# Adafruit_NeoPixel_8_Stick.net
KiCad netlist of a schematic drawn in EAGLE
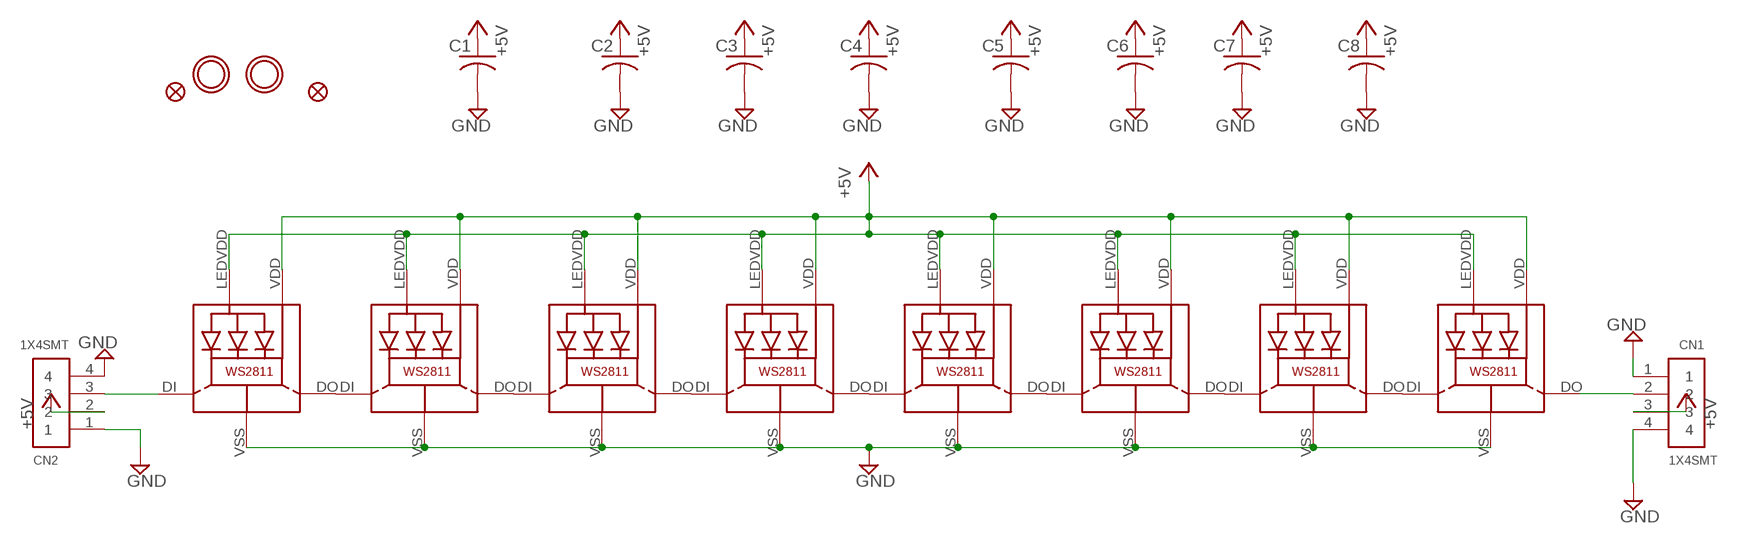
[diagram p0: schematic, sheet 1]

(export (version "E")
  (design (tool "Eeschema 10.0.6"))
  (components
    (comp (ref "C1")
      (value "C-USC0805K")
      (footprint "eagle-import:C0805K")
      (libsource (lib "eagle-import") (part "C-USC0805K"))
    )
    (comp (ref "C2")
      (value "C-USC0805K")
      (footprint "eagle-import:C0805K")
      (libsource (lib "eagle-import") (part "C-USC0805K"))
    )
    (comp (ref "C3")
      (value "C-USC0805K")
      (footprint "eagle-import:C0805K")
      (libsource (lib "eagle-import") (part "C-USC0805K"))
    )
    (comp (ref "C4")
      (value "C-USC0805K")
      (footprint "eagle-import:C0805K")
      (libsource (lib "eagle-import") (part "C-USC0805K"))
    )
    (comp (ref "C5")
      (value "C-USC0805K")
      (footprint "eagle-import:C0805K")
      (libsource (lib "eagle-import") (part "C-USC0805K"))
    )
    (comp (ref "C6")
      (value "C-USC0805K")
      (footprint "eagle-import:C0805K")
      (libsource (lib "eagle-import") (part "C-USC0805K"))
    )
    (comp (ref "C7")
      (value "C-USC0805K")
      (footprint "eagle-import:C0805K")
      (libsource (lib "eagle-import") (part "C-USC0805K"))
    )
    (comp (ref "C8")
      (value "C-USC0805K")
      (footprint "eagle-import:C0805K")
      (libsource (lib "eagle-import") (part "C-USC0805K"))
    )
    (comp (ref "CN1")
      (value "1X4SMT")
      (footprint "eagle-import:1X4-SMT")
      (libsource (lib "eagle-import") (part "1X4SMT"))
    )
    (comp (ref "CN2")
      (value "1X4SMT")
      (footprint "eagle-import:1X4-SMT")
      (libsource (lib "eagle-import") (part "1X4SMT"))
    )
    (comp (ref "FID1")
      (value "FIDUCIAL\"\"")
      (footprint "eagle-import:FIDUCIAL_1MM")
      (libsource (lib "eagle-import") (part "FIDUCIAL{dblquote}{dblquote}"))
    )
    (comp (ref "FID3")
      (value "FIDUCIAL\"\"")
      (footprint "eagle-import:FIDUCIAL_1MM")
      (libsource (lib "eagle-import") (part "FIDUCIAL{dblquote}{dblquote}"))
    )
    (comp (ref "LED1")
      (value "WS28115050")
      (footprint "eagle-import:WS28115050")
      (libsource (lib "eagle-import") (part "WS28115050"))
    )
    (comp (ref "LED2")
      (value "WS28115050")
      (footprint "eagle-import:WS28115050")
      (libsource (lib "eagle-import") (part "WS28115050"))
    )
    (comp (ref "LED3")
      (value "WS28115050")
      (footprint "eagle-import:WS28115050")
      (libsource (lib "eagle-import") (part "WS28115050"))
    )
    (comp (ref "LED4")
      (value "WS28115050")
      (footprint "eagle-import:WS28115050")
      (libsource (lib "eagle-import") (part "WS28115050"))
    )
    (comp (ref "LED5")
      (value "WS28115050")
      (footprint "eagle-import:WS28115050")
      (libsource (lib "eagle-import") (part "WS28115050"))
    )
    (comp (ref "LED6")
      (value "WS28115050")
      (footprint "eagle-import:WS28115050")
      (libsource (lib "eagle-import") (part "WS28115050"))
    )
    (comp (ref "LED7")
      (value "WS28115050")
      (footprint "eagle-import:WS28115050")
      (libsource (lib "eagle-import") (part "WS28115050"))
    )
    (comp (ref "LED8")
      (value "WS28115050")
      (footprint "eagle-import:WS28115050")
      (libsource (lib "eagle-import") (part "WS28115050"))
    )
    (comp (ref "U$2")
      (value "MOUNTINGHOLE2.0")
      (footprint "eagle-import:MOUNTINGHOLE_2.0_PLATED")
      (libsource (lib "eagle-import") (part "MOUNTINGHOLE2.0"))
    )
    (comp (ref "U$3")
      (value "MOUNTINGHOLE2.0")
      (footprint "eagle-import:MOUNTINGHOLE_2.0_PLATED")
      (libsource (lib "eagle-import") (part "MOUNTINGHOLE2.0"))
    )
  )
  (nets
    (net (code "1") (name "+5V") (class "Default")
      (node (ref "C1") (pin "1") (pinfunction "1_1") (pintype "passive"))
      (node (ref "C2") (pin "1") (pinfunction "1_1") (pintype "passive"))
      (node (ref "C3") (pin "1") (pinfunction "1_1") (pintype "passive"))
      (node (ref "C4") (pin "1") (pinfunction "1_1") (pintype "passive"))
      (node (ref "C5") (pin "1") (pinfunction "1_1") (pintype "passive"))
      (node (ref "C6") (pin "1") (pinfunction "1_1") (pintype "passive"))
      (node (ref "C7") (pin "1") (pinfunction "1_1") (pintype "passive"))
      (node (ref "C8") (pin "1") (pinfunction "1_1") (pintype "passive"))
      (node (ref "CN1") (pin "3") (pinfunction "3_3") (pintype "bidirectional"))
      (node (ref "CN2") (pin "2") (pinfunction "2_2") (pintype "bidirectional"))
      (node (ref "LED1") (pin "LEDVDD") (pinfunction "LEDVDD_LEDVDD") (pintype "power_in"))
      (node (ref "LED1") (pin "VDD") (pinfunction "VDD_VDD") (pintype "power_in"))
      (node (ref "LED2") (pin "LEDVDD") (pinfunction "LEDVDD_LEDVDD") (pintype "power_in"))
      (node (ref "LED2") (pin "VDD") (pinfunction "VDD_VDD") (pintype "power_in"))
      (node (ref "LED3") (pin "LEDVDD") (pinfunction "LEDVDD_LEDVDD") (pintype "power_in"))
      (node (ref "LED3") (pin "VDD") (pinfunction "VDD_VDD") (pintype "power_in"))
      (node (ref "LED4") (pin "LEDVDD") (pinfunction "LEDVDD_LEDVDD") (pintype "power_in"))
      (node (ref "LED4") (pin "VDD") (pinfunction "VDD_VDD") (pintype "power_in"))
      (node (ref "LED5") (pin "LEDVDD") (pinfunction "LEDVDD_LEDVDD") (pintype "power_in"))
      (node (ref "LED5") (pin "VDD") (pinfunction "VDD_VDD") (pintype "power_in"))
      (node (ref "LED6") (pin "LEDVDD") (pinfunction "LEDVDD_LEDVDD") (pintype "power_in"))
      (node (ref "LED6") (pin "VDD") (pinfunction "VDD_VDD") (pintype "power_in"))
      (node (ref "LED7") (pin "LEDVDD") (pinfunction "LEDVDD_LEDVDD") (pintype "power_in"))
      (node (ref "LED7") (pin "VDD") (pinfunction "VDD_VDD") (pintype "power_in"))
      (node (ref "LED8") (pin "LEDVDD") (pinfunction "LEDVDD_LEDVDD") (pintype "power_in"))
      (node (ref "LED8") (pin "VDD") (pinfunction "VDD_VDD") (pintype "power_in"))
    )
    (net (code "2") (name "GND") (class "Default")
      (node (ref "C1") (pin "2") (pinfunction "2_2") (pintype "passive"))
      (node (ref "C2") (pin "2") (pinfunction "2_2") (pintype "passive"))
      (node (ref "C3") (pin "2") (pinfunction "2_2") (pintype "passive"))
      (node (ref "C4") (pin "2") (pinfunction "2_2") (pintype "passive"))
      (node (ref "C5") (pin "2") (pinfunction "2_2") (pintype "passive"))
      (node (ref "C6") (pin "2") (pinfunction "2_2") (pintype "passive"))
      (node (ref "C7") (pin "2") (pinfunction "2_2") (pintype "passive"))
      (node (ref "C8") (pin "2") (pinfunction "2_2") (pintype "passive"))
      (node (ref "CN1") (pin "1") (pinfunction "1_1") (pintype "bidirectional"))
      (node (ref "CN1") (pin "4") (pinfunction "4_4") (pintype "bidirectional"))
      (node (ref "CN2") (pin "1") (pinfunction "1_1") (pintype "bidirectional"))
      (node (ref "CN2") (pin "4") (pinfunction "4_4") (pintype "bidirectional"))
      (node (ref "LED1") (pin "VSS") (pinfunction "GND_VSS") (pintype "power_in"))
      (node (ref "LED2") (pin "VSS") (pinfunction "GND_VSS") (pintype "power_in"))
      (node (ref "LED3") (pin "VSS") (pinfunction "GND_VSS") (pintype "power_in"))
      (node (ref "LED4") (pin "VSS") (pinfunction "GND_VSS") (pintype "power_in"))
      (node (ref "LED5") (pin "VSS") (pinfunction "GND_VSS") (pintype "power_in"))
      (node (ref "LED6") (pin "VSS") (pinfunction "GND_VSS") (pintype "power_in"))
      (node (ref "LED7") (pin "VSS") (pinfunction "GND_VSS") (pintype "power_in"))
      (node (ref "LED8") (pin "VSS") (pinfunction "GND_VSS") (pintype "power_in"))
    )
    (net (code "3") (name "Net-(CN1-Pad2)") (class "Default")
      (node (ref "CN1") (pin "2") (pinfunction "2_2") (pintype "bidirectional"))
      (node (ref "LED8") (pin "DO") (pinfunction "DO_DO") (pintype "output"))
    )
    (net (code "4") (name "Net-(CN2-Pad3)") (class "Default")
      (node (ref "CN2") (pin "3") (pinfunction "3_3") (pintype "bidirectional"))
      (node (ref "LED1") (pin "DI") (pinfunction "DI_DI") (pintype "input"))
    )
    (net (code "5") (name "Net-(LED1-PadDO)") (class "Default")
      (node (ref "LED1") (pin "DO") (pinfunction "DO_DO") (pintype "output"))
      (node (ref "LED2") (pin "DI") (pinfunction "DI_DI") (pintype "input"))
    )
    (net (code "6") (name "Net-(LED2-PadDO)") (class "Default")
      (node (ref "LED2") (pin "DO") (pinfunction "DO_DO") (pintype "output"))
      (node (ref "LED3") (pin "DI") (pinfunction "DI_DI") (pintype "input"))
    )
    (net (code "7") (name "Net-(LED3-PadDO)") (class "Default")
      (node (ref "LED3") (pin "DO") (pinfunction "DO_DO") (pintype "output"))
      (node (ref "LED4") (pin "DI") (pinfunction "DI_DI") (pintype "input"))
    )
    (net (code "8") (name "Net-(LED4-PadDO)") (class "Default")
      (node (ref "LED4") (pin "DO") (pinfunction "DO_DO") (pintype "output"))
      (node (ref "LED5") (pin "DI") (pinfunction "DI_DI") (pintype "input"))
    )
    (net (code "9") (name "Net-(LED5-PadDO)") (class "Default")
      (node (ref "LED5") (pin "DO") (pinfunction "DO_DO") (pintype "output"))
      (node (ref "LED6") (pin "DI") (pinfunction "DI_DI") (pintype "input"))
    )
    (net (code "10") (name "Net-(LED6-PadDO)") (class "Default")
      (node (ref "LED6") (pin "DO") (pinfunction "DO_DO") (pintype "output"))
      (node (ref "LED7") (pin "DI") (pinfunction "DI_DI") (pintype "input"))
    )
    (net (code "11") (name "Net-(LED7-PadDO)") (class "Default")
      (node (ref "LED7") (pin "DO") (pinfunction "DO_DO") (pintype "output"))
      (node (ref "LED8") (pin "DI") (pinfunction "DI_DI") (pintype "input"))
    )
  )
)
